# VKeyVoltageKeypad.net
KiCad netlist of a schematic drawn in EAGLE
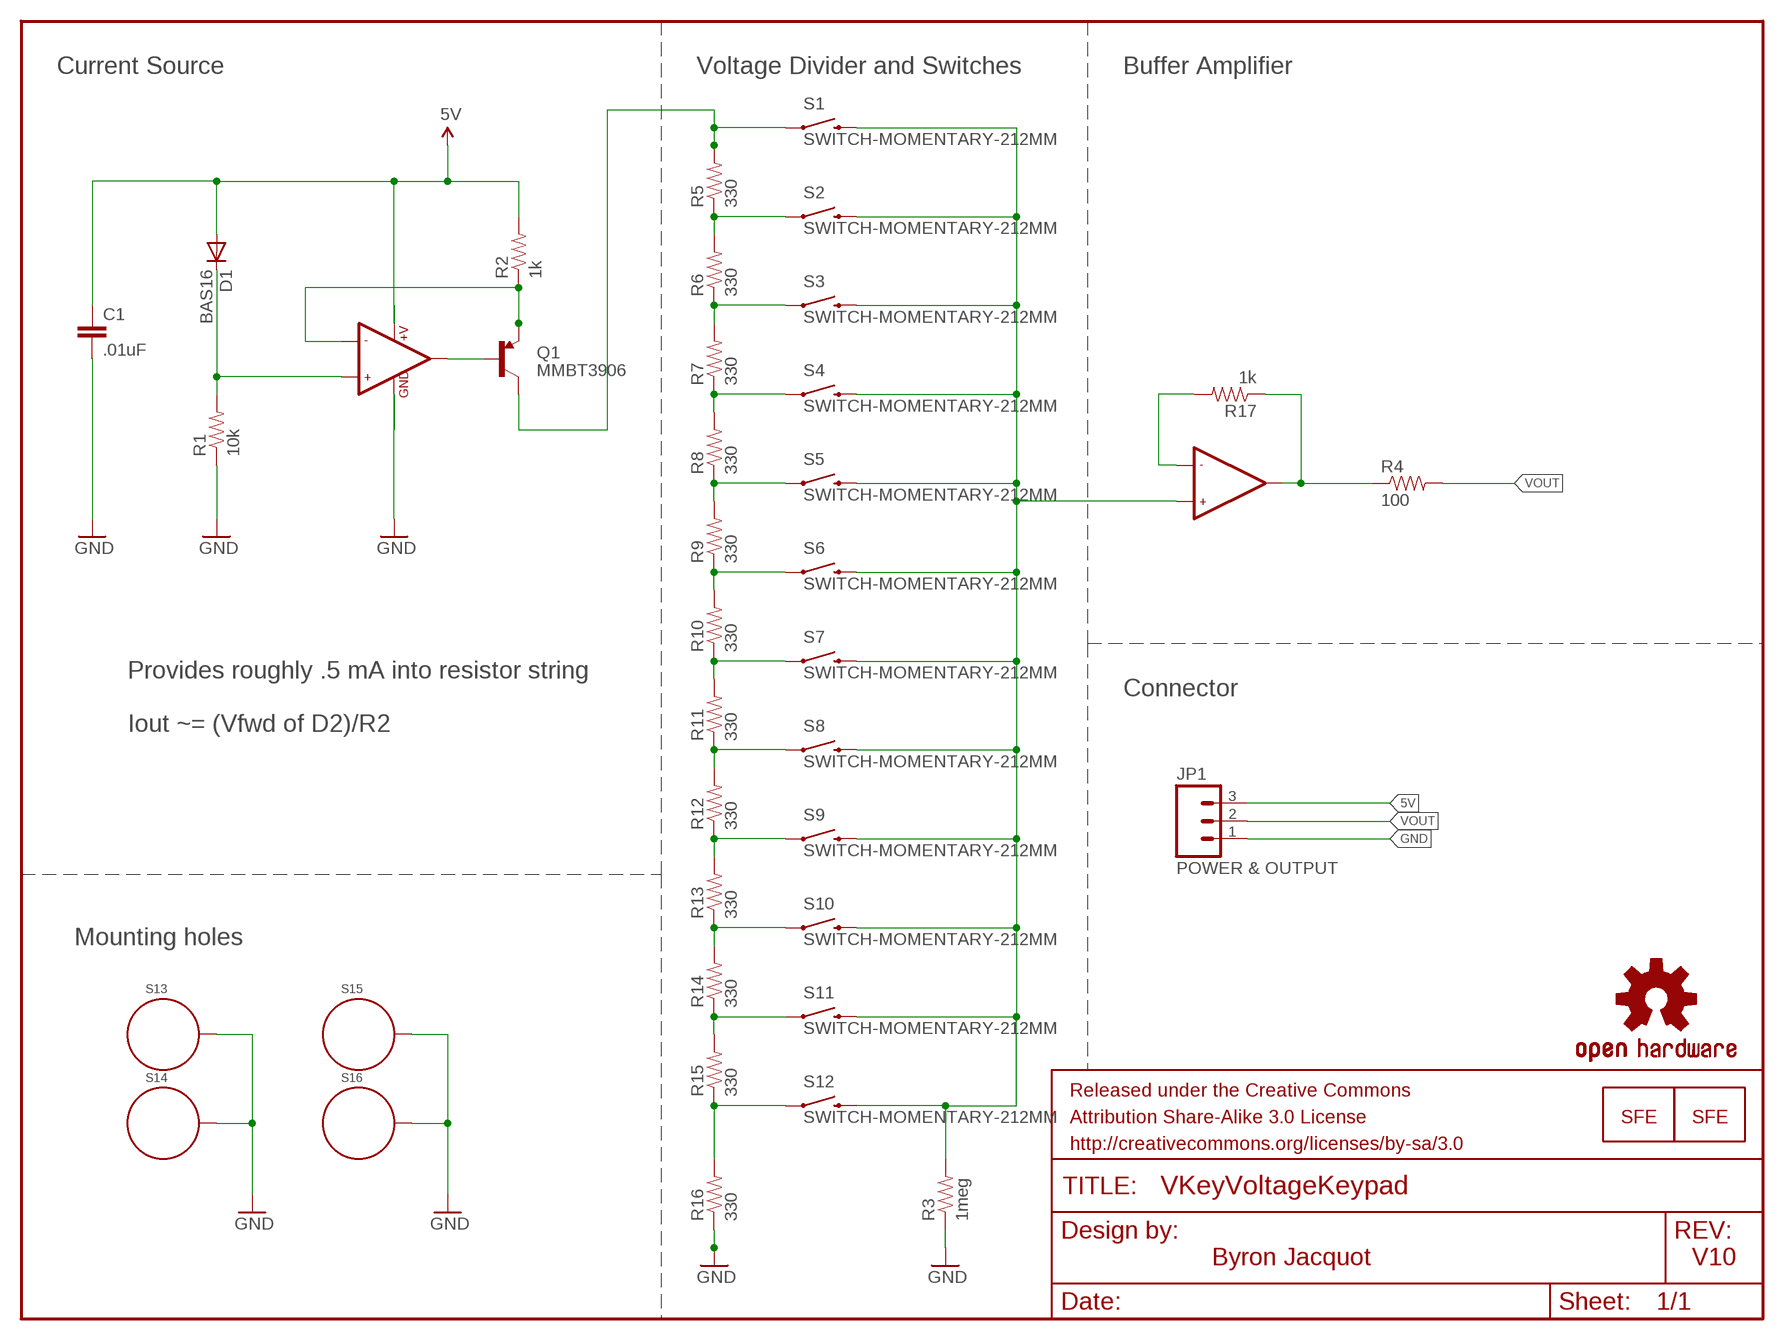
[diagram p0: schematic, sheet 1]

(export (version "E")
  (design (tool "Eeschema 10.0.6"))
  (components
    (comp (ref "C1")
      (value ".01uF")
      (footprint "eagle-import:0603-CAP")
      (libsource (lib "eagle-import") (part "10NF/10000PF-50V-10%(0603)"))
    )
    (comp (ref "D1")
      (value "BAS16")
      (footprint "eagle-import:SOD-323")
      (libsource (lib "eagle-import") (part "DIODESOD"))
    )
    (comp (ref "FRAME1")
      (value "FRAME-LETTER")
      (footprint "eagle-import:CREATIVE_COMMONS")
      (libsource (lib "eagle-import") (part "FRAME-LETTER"))
    )
    (comp (ref "JP1")
      (value "POWER & OUTPUT")
      (footprint "eagle-import:1X03_NO_SILK")
      (libsource (lib "eagle-import") (part "M031X03_NO_SILK"))
    )
    (comp (ref "LOGO1")
      (value "LOGO-SFENEW")
      (footprint "eagle-import:SFE-NEW-WEBLOGO")
      (libsource (lib "eagle-import") (part "LOGO-SFENEW"))
    )
    (comp (ref "LOGO2")
      (value "LOGO-SFENEW")
      (footprint "eagle-import:SFE-NEW-WEBLOGO")
      (libsource (lib "eagle-import") (part "LOGO-SFENEW"))
    )
    (comp (ref "LOGO3")
      (value "OSHW-LOGOM")
      (footprint "eagle-import:OSHW-LOGO-M")
      (libsource (lib "eagle-import") (part "OSHW-LOGOM"))
    )
    (comp (ref "LOGO4")
      (value "OSHW-LOGOL")
      (footprint "eagle-import:OSHW-LOGO-L")
      (libsource (lib "eagle-import") (part "OSHW-LOGOL"))
    )
    (comp (ref "Q1")
      (value "MMBT3906")
      (footprint "eagle-import:SOT23")
      (libsource (lib "eagle-import") (part "TRANSISTOR_PNPMMBT3906"))
    )
    (comp (ref "R1")
      (value "10k")
      (footprint "eagle-import:0603-RES")
      (libsource (lib "eagle-import") (part "10KOHM1/10W1%(0603)0603"))
    )
    (comp (ref "R2")
      (value "1k")
      (footprint "eagle-import:0603-RES")
      (libsource (lib "eagle-import") (part "1KOHM1/10W1%(0603)"))
    )
    (comp (ref "R3")
      (value "1meg")
      (footprint "eagle-import:0603-RES")
      (libsource (lib "eagle-import") (part "1M-1%"))
    )
    (comp (ref "R4")
      (value "100")
      (footprint "eagle-import:0603-RES")
      (libsource (lib "eagle-import") (part "100OHM1/10W1%(0603)"))
    )
    (comp (ref "R5")
      (value "330")
      (footprint "eagle-import:0603-RES")
      (libsource (lib "eagle-import") (part "330OHM1/10W1%(0603)"))
    )
    (comp (ref "R6")
      (value "330")
      (footprint "eagle-import:0603-RES")
      (fields (field (name "PROD_ID") "RES-00818"))
      (libsource (lib "eagle-import") (part "330OHM1/10W1%(0603)"))
    )
    (comp (ref "R7")
      (value "330")
      (footprint "eagle-import:0603-RES")
      (fields (field (name "PROD_ID") "RES-00818"))
      (libsource (lib "eagle-import") (part "330OHM1/10W1%(0603)"))
    )
    (comp (ref "R8")
      (value "330")
      (footprint "eagle-import:0603-RES")
      (fields (field (name "PROD_ID") "RES-00818"))
      (libsource (lib "eagle-import") (part "330OHM1/10W1%(0603)"))
    )
    (comp (ref "R9")
      (value "330")
      (footprint "eagle-import:0603-RES")
      (fields (field (name "PROD_ID") "RES-00818"))
      (libsource (lib "eagle-import") (part "330OHM1/10W1%(0603)"))
    )
    (comp (ref "R10")
      (value "330")
      (footprint "eagle-import:0603-RES")
      (fields (field (name "PROD_ID") "RES-00818"))
      (libsource (lib "eagle-import") (part "330OHM1/10W1%(0603)"))
    )
    (comp (ref "R11")
      (value "330")
      (footprint "eagle-import:0603-RES")
      (fields (field (name "PROD_ID") "RES-00818"))
      (libsource (lib "eagle-import") (part "330OHM1/10W1%(0603)"))
    )
    (comp (ref "R12")
      (value "330")
      (footprint "eagle-import:0603-RES")
      (fields (field (name "PROD_ID") "RES-00818"))
      (libsource (lib "eagle-import") (part "330OHM1/10W1%(0603)"))
    )
    (comp (ref "R13")
      (value "330")
      (footprint "eagle-import:0603-RES")
      (fields (field (name "PROD_ID") "RES-00818"))
      (libsource (lib "eagle-import") (part "330OHM1/10W1%(0603)"))
    )
    (comp (ref "R14")
      (value "330")
      (footprint "eagle-import:0603-RES")
      (fields (field (name "PROD_ID") "RES-00818"))
      (libsource (lib "eagle-import") (part "330OHM1/10W1%(0603)"))
    )
    (comp (ref "R15")
      (value "330")
      (footprint "eagle-import:0603-RES")
      (fields (field (name "PROD_ID") "RES-00818"))
      (libsource (lib "eagle-import") (part "330OHM1/10W1%(0603)"))
    )
    (comp (ref "R16")
      (value "330")
      (footprint "eagle-import:0603-RES")
      (fields (field (name "PROD_ID") "RES-00818"))
      (libsource (lib "eagle-import") (part "330OHM1/10W1%(0603)"))
    )
    (comp (ref "R17")
      (value "1k")
      (footprint "eagle-import:0603-RES")
      (libsource (lib "eagle-import") (part "1KOHM1/10W1%(0603)"))
    )
    (comp (ref "S1")
      (value "SWITCH-MOMENTARY-212MM")
      (footprint "eagle-import:TACTILE-PTH-12MM")
      (libsource (lib "eagle-import") (part "SWITCH-MOMENTARY-212MM"))
    )
    (comp (ref "S2")
      (value "SWITCH-MOMENTARY-212MM")
      (footprint "eagle-import:TACTILE-PTH-12MM")
      (libsource (lib "eagle-import") (part "SWITCH-MOMENTARY-212MM"))
    )
    (comp (ref "S3")
      (value "SWITCH-MOMENTARY-212MM")
      (footprint "eagle-import:TACTILE-PTH-12MM")
      (libsource (lib "eagle-import") (part "SWITCH-MOMENTARY-212MM"))
    )
    (comp (ref "S4")
      (value "SWITCH-MOMENTARY-212MM")
      (footprint "eagle-import:TACTILE-PTH-12MM")
      (libsource (lib "eagle-import") (part "SWITCH-MOMENTARY-212MM"))
    )
    (comp (ref "S5")
      (value "SWITCH-MOMENTARY-212MM")
      (footprint "eagle-import:TACTILE-PTH-12MM")
      (libsource (lib "eagle-import") (part "SWITCH-MOMENTARY-212MM"))
    )
    (comp (ref "S6")
      (value "SWITCH-MOMENTARY-212MM")
      (footprint "eagle-import:TACTILE-PTH-12MM")
      (libsource (lib "eagle-import") (part "SWITCH-MOMENTARY-212MM"))
    )
    (comp (ref "S7")
      (value "SWITCH-MOMENTARY-212MM")
      (footprint "eagle-import:TACTILE-PTH-12MM")
      (libsource (lib "eagle-import") (part "SWITCH-MOMENTARY-212MM"))
    )
    (comp (ref "S8")
      (value "SWITCH-MOMENTARY-212MM")
      (footprint "eagle-import:TACTILE-PTH-12MM")
      (libsource (lib "eagle-import") (part "SWITCH-MOMENTARY-212MM"))
    )
    (comp (ref "S9")
      (value "SWITCH-MOMENTARY-212MM")
      (footprint "eagle-import:TACTILE-PTH-12MM")
      (libsource (lib "eagle-import") (part "SWITCH-MOMENTARY-212MM"))
    )
    (comp (ref "S10")
      (value "SWITCH-MOMENTARY-212MM")
      (footprint "eagle-import:TACTILE-PTH-12MM")
      (libsource (lib "eagle-import") (part "SWITCH-MOMENTARY-212MM"))
    )
    (comp (ref "S11")
      (value "SWITCH-MOMENTARY-212MM")
      (footprint "eagle-import:TACTILE-PTH-12MM")
      (libsource (lib "eagle-import") (part "SWITCH-MOMENTARY-212MM"))
    )
    (comp (ref "S12")
      (value "SWITCH-MOMENTARY-212MM")
      (footprint "eagle-import:TACTILE-PTH-12MM")
      (libsource (lib "eagle-import") (part "SWITCH-MOMENTARY-212MM"))
    )
    (comp (ref "S13")
      (value "STANDOFF_ELECTRICAL")
      (footprint "eagle-import:STANDOFF-ELECTRICAL")
      (libsource (lib "eagle-import") (part "STANDOFF_ELECTRICAL"))
    )
    (comp (ref "S14")
      (value "STANDOFF_ELECTRICAL")
      (footprint "eagle-import:STANDOFF-ELECTRICAL")
      (libsource (lib "eagle-import") (part "STANDOFF_ELECTRICAL"))
    )
    (comp (ref "S15")
      (value "STANDOFF_ELECTRICAL")
      (footprint "eagle-import:STANDOFF-ELECTRICAL")
      (libsource (lib "eagle-import") (part "STANDOFF_ELECTRICAL"))
    )
    (comp (ref "S16")
      (value "STANDOFF_ELECTRICAL")
      (footprint "eagle-import:STANDOFF-ELECTRICAL")
      (libsource (lib "eagle-import") (part "STANDOFF_ELECTRICAL"))
    )
    (comp (ref "U1")
      (value "LMV358")
      (footprint "eagle-import:SO08")
      (libsource (lib "eagle-import") (part "LMV358"))
    )
  )
  (nets
    (net (code "1") (name "5V") (class "Default")
      (node (ref "C1") (pin "1") (pinfunction "1_1") (pintype "passive"))
      (node (ref "D1") (pin "2") (pinfunction "A_2") (pintype "passive"))
      (node (ref "JP1") (pin "3") (pinfunction "3_3") (pintype "passive"))
      (node (ref "R2") (pin "2") (pinfunction "2_2") (pintype "passive"))
      (node (ref "U1") (pin "8") (pinfunction "+V_8") (pintype "power_in"))
    )
    (net (code "2") (name "GND") (class "Default")
      (node (ref "C1") (pin "2") (pinfunction "2_2") (pintype "passive"))
      (node (ref "JP1") (pin "1") (pinfunction "1_1") (pintype "passive"))
      (node (ref "R1") (pin "1") (pinfunction "1_1") (pintype "passive"))
      (node (ref "R16") (pin "1") (pinfunction "1_1") (pintype "passive"))
      (node (ref "R3") (pin "1") (pinfunction "1_1") (pintype "passive"))
      (node (ref "S13") (pin "P1") (pinfunction "P$1_P1") (pintype "bidirectional"))
      (node (ref "S14") (pin "P1") (pinfunction "P$1_P1") (pintype "bidirectional"))
      (node (ref "S15") (pin "P1") (pinfunction "P$1_P1") (pintype "bidirectional"))
      (node (ref "S16") (pin "P1") (pinfunction "P$1_P1") (pintype "bidirectional"))
      (node (ref "U1") (pin "4") (pinfunction "GND_4") (pintype "power_in"))
    )
    (net (code "3") (name "Net-(D1-C)") (class "Default")
      (node (ref "D1") (pin "1") (pinfunction "C_1") (pintype "passive"))
      (node (ref "R1") (pin "2") (pinfunction "2_2") (pintype "passive"))
      (node (ref "U1") (pin "3") (pinfunction "+IN1_3") (pintype "input"))
    )
    (net (code "4") (name "Net-(Q1-B)") (class "Default")
      (node (ref "Q1") (pin "1") (pinfunction "B_1") (pintype "passive"))
      (node (ref "U1") (pin "1") (pinfunction "OUT1_1") (pintype "output"))
    )
    (net (code "5") (name "Net-(Q1-C)") (class "Default")
      (node (ref "Q1") (pin "3") (pinfunction "C_3") (pintype "passive"))
      (node (ref "R5") (pin "2") (pinfunction "2_2") (pintype "passive"))
      (node (ref "S1") (pin "1") (pinfunction "1_1") (pintype "passive"))
    )
    (net (code "6") (name "Net-(Q1-E)") (class "Default")
      (node (ref "Q1") (pin "2") (pinfunction "E_2") (pintype "passive"))
      (node (ref "R2") (pin "1") (pinfunction "1_1") (pintype "passive"))
      (node (ref "U1") (pin "2") (pinfunction "-IN1_2") (pintype "input"))
    )
    (net (code "7") (name "Net-(R5-Pad1)") (class "Default")
      (node (ref "R5") (pin "1") (pinfunction "1_1") (pintype "passive"))
      (node (ref "R6") (pin "2") (pinfunction "2_2") (pintype "passive"))
      (node (ref "S2") (pin "1") (pinfunction "1_1") (pintype "passive"))
    )
    (net (code "8") (name "Net-(R6-Pad1)") (class "Default")
      (node (ref "R6") (pin "1") (pinfunction "1_1") (pintype "passive"))
      (node (ref "R7") (pin "2") (pinfunction "2_2") (pintype "passive"))
      (node (ref "S3") (pin "1") (pinfunction "1_1") (pintype "passive"))
    )
    (net (code "9") (name "Net-(R7-Pad1)") (class "Default")
      (node (ref "R7") (pin "1") (pinfunction "1_1") (pintype "passive"))
      (node (ref "R8") (pin "2") (pinfunction "2_2") (pintype "passive"))
      (node (ref "S4") (pin "1") (pinfunction "1_1") (pintype "passive"))
    )
    (net (code "10") (name "Net-(R8-Pad1)") (class "Default")
      (node (ref "R8") (pin "1") (pinfunction "1_1") (pintype "passive"))
      (node (ref "R9") (pin "2") (pinfunction "2_2") (pintype "passive"))
      (node (ref "S5") (pin "1") (pinfunction "1_1") (pintype "passive"))
    )
    (net (code "11") (name "Net-(R10-Pad1)") (class "Default")
      (node (ref "R10") (pin "1") (pinfunction "1_1") (pintype "passive"))
      (node (ref "R11") (pin "2") (pinfunction "2_2") (pintype "passive"))
      (node (ref "S7") (pin "1") (pinfunction "1_1") (pintype "passive"))
    )
    (net (code "12") (name "Net-(R10-Pad2)") (class "Default")
      (node (ref "R10") (pin "2") (pinfunction "2_2") (pintype "passive"))
      (node (ref "R9") (pin "1") (pinfunction "1_1") (pintype "passive"))
      (node (ref "S6") (pin "1") (pinfunction "1_1") (pintype "passive"))
    )
    (net (code "13") (name "Net-(R11-Pad1)") (class "Default")
      (node (ref "R11") (pin "1") (pinfunction "1_1") (pintype "passive"))
      (node (ref "R12") (pin "2") (pinfunction "2_2") (pintype "passive"))
      (node (ref "S8") (pin "1") (pinfunction "1_1") (pintype "passive"))
    )
    (net (code "14") (name "Net-(R12-Pad1)") (class "Default")
      (node (ref "R12") (pin "1") (pinfunction "1_1") (pintype "passive"))
      (node (ref "R13") (pin "2") (pinfunction "2_2") (pintype "passive"))
      (node (ref "S9") (pin "1") (pinfunction "1_1") (pintype "passive"))
    )
    (net (code "15") (name "Net-(R13-Pad1)") (class "Default")
      (node (ref "R13") (pin "1") (pinfunction "1_1") (pintype "passive"))
      (node (ref "R14") (pin "2") (pinfunction "2_2") (pintype "passive"))
      (node (ref "S10") (pin "1") (pinfunction "1_1") (pintype "passive"))
    )
    (net (code "16") (name "Net-(R14-Pad1)") (class "Default")
      (node (ref "R14") (pin "1") (pinfunction "1_1") (pintype "passive"))
      (node (ref "R15") (pin "2") (pinfunction "2_2") (pintype "passive"))
      (node (ref "S11") (pin "1") (pinfunction "1_1") (pintype "passive"))
    )
    (net (code "17") (name "Net-(R15-Pad1)") (class "Default")
      (node (ref "R15") (pin "1") (pinfunction "1_1") (pintype "passive"))
      (node (ref "R16") (pin "2") (pinfunction "2_2") (pintype "passive"))
      (node (ref "S12") (pin "1") (pinfunction "1_1") (pintype "passive"))
    )
    (net (code "18") (name "Net-(S1-2)") (class "Default")
      (node (ref "R3") (pin "2") (pinfunction "2_2") (pintype "passive"))
      (node (ref "S1") (pin "3") (pinfunction "2_3") (pintype "passive"))
      (node (ref "S10") (pin "3") (pinfunction "2_3") (pintype "passive"))
      (node (ref "S11") (pin "3") (pinfunction "2_3") (pintype "passive"))
      (node (ref "S12") (pin "3") (pinfunction "2_3") (pintype "passive"))
      (node (ref "S2") (pin "3") (pinfunction "2_3") (pintype "passive"))
      (node (ref "S3") (pin "3") (pinfunction "2_3") (pintype "passive"))
      (node (ref "S4") (pin "3") (pinfunction "2_3") (pintype "passive"))
      (node (ref "S5") (pin "3") (pinfunction "2_3") (pintype "passive"))
      (node (ref "S6") (pin "3") (pinfunction "2_3") (pintype "passive"))
      (node (ref "S7") (pin "3") (pinfunction "2_3") (pintype "passive"))
      (node (ref "S8") (pin "3") (pinfunction "2_3") (pintype "passive"))
      (node (ref "S9") (pin "3") (pinfunction "2_3") (pintype "passive"))
      (node (ref "U1") (pin "5") (pinfunction "+IN2_5") (pintype "input"))
    )
    (net (code "19") (name "Net-(U1B--IN2)") (class "Default")
      (node (ref "R17") (pin "2") (pinfunction "2_2") (pintype "passive"))
      (node (ref "U1") (pin "6") (pinfunction "-IN2_6") (pintype "input"))
    )
    (net (code "20") (name "Net-(U1B-OUT2)") (class "Default")
      (node (ref "R17") (pin "1") (pinfunction "1_1") (pintype "passive"))
      (node (ref "R4") (pin "1") (pinfunction "1_1") (pintype "passive"))
      (node (ref "U1") (pin "7") (pinfunction "OUT2_7") (pintype "output"))
    )
    (net (code "21") (name "VOUT") (class "Default")
      (node (ref "JP1") (pin "2") (pinfunction "2_2") (pintype "passive"))
      (node (ref "R4") (pin "2") (pinfunction "2_2") (pintype "passive"))
    )
  )
)
